# main_v3.net
KiCad netlist of a schematic drawn in EAGLE
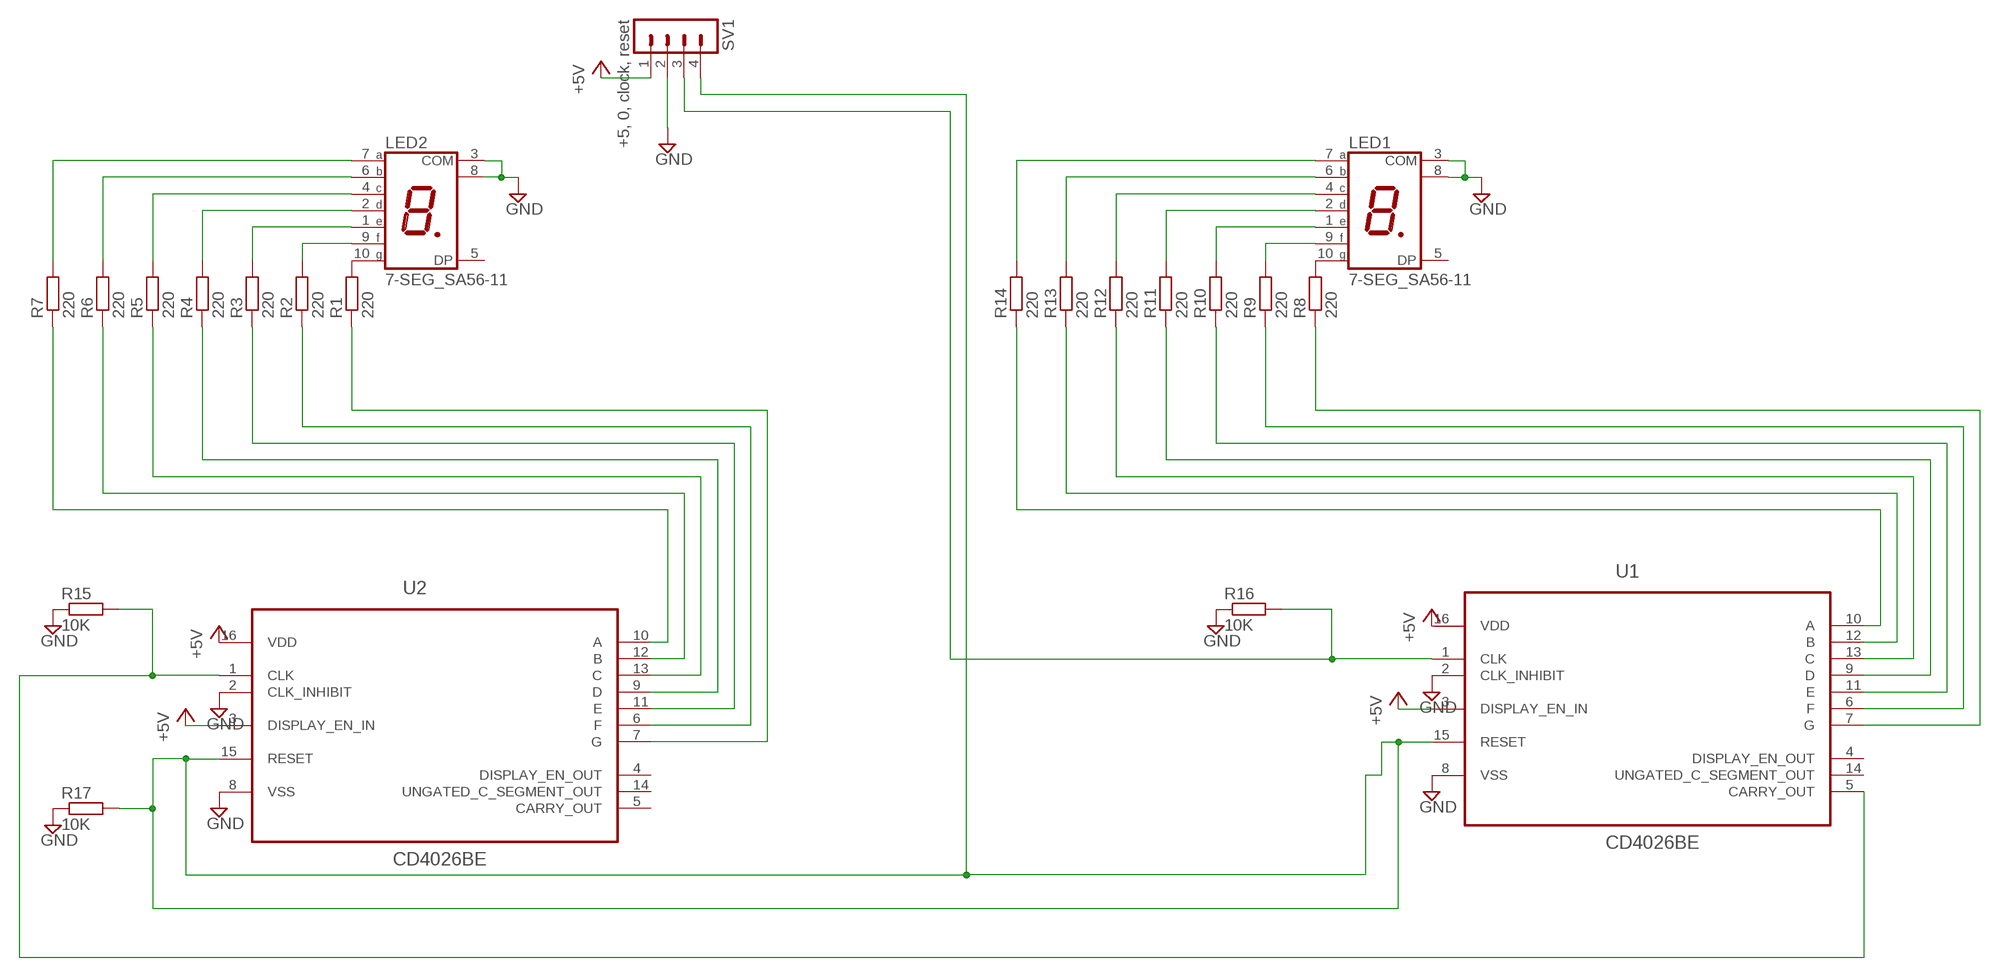
[diagram p0: schematic, sheet 1]

(export (version "E")
  (design (tool "Eeschema 10.0.6"))
  (components
    (comp (ref "LED1")
      (value "7-SEG_SA56-11")
      (footprint "eagle-import:SA56-11")
      (libsource (lib "eagle-import") (part "7-SEG_SA56-11"))
    )
    (comp (ref "LED2")
      (value "7-SEG_SA56-11")
      (footprint "eagle-import:SA56-11")
      (libsource (lib "eagle-import") (part "7-SEG_SA56-11"))
    )
    (comp (ref "R1")
      (value "220")
      (footprint "eagle-import:R0805")
      (libsource (lib "eagle-import") (part "R-EU_R0805"))
    )
    (comp (ref "R2")
      (value "220")
      (footprint "eagle-import:R0805")
      (libsource (lib "eagle-import") (part "R-EU_R0805"))
    )
    (comp (ref "R3")
      (value "220")
      (footprint "eagle-import:R0805")
      (libsource (lib "eagle-import") (part "R-EU_R0805"))
    )
    (comp (ref "R4")
      (value "220")
      (footprint "eagle-import:R0805")
      (libsource (lib "eagle-import") (part "R-EU_R0805"))
    )
    (comp (ref "R5")
      (value "220")
      (footprint "eagle-import:R0805")
      (libsource (lib "eagle-import") (part "R-EU_R0805"))
    )
    (comp (ref "R6")
      (value "220")
      (footprint "eagle-import:R0805")
      (libsource (lib "eagle-import") (part "R-EU_R0805"))
    )
    (comp (ref "R7")
      (value "220")
      (footprint "eagle-import:R0805")
      (libsource (lib "eagle-import") (part "R-EU_R0805"))
    )
    (comp (ref "R8")
      (value "220")
      (footprint "eagle-import:R0805")
      (libsource (lib "eagle-import") (part "R-EU_R0805"))
    )
    (comp (ref "R9")
      (value "220")
      (footprint "eagle-import:R0805")
      (libsource (lib "eagle-import") (part "R-EU_R0805"))
    )
    (comp (ref "R10")
      (value "220")
      (footprint "eagle-import:R0805")
      (libsource (lib "eagle-import") (part "R-EU_R0805"))
    )
    (comp (ref "R11")
      (value "220")
      (footprint "eagle-import:R0805")
      (libsource (lib "eagle-import") (part "R-EU_R0805"))
    )
    (comp (ref "R12")
      (value "220")
      (footprint "eagle-import:R0805")
      (libsource (lib "eagle-import") (part "R-EU_R0805"))
    )
    (comp (ref "R13")
      (value "220")
      (footprint "eagle-import:R0805")
      (libsource (lib "eagle-import") (part "R-EU_R0805"))
    )
    (comp (ref "R14")
      (value "220")
      (footprint "eagle-import:R0805")
      (libsource (lib "eagle-import") (part "R-EU_R0805"))
    )
    (comp (ref "R15")
      (value "10K")
      (footprint "eagle-import:R0805")
      (libsource (lib "eagle-import") (part "R-EU_R0805"))
    )
    (comp (ref "R16")
      (value "10K")
      (footprint "eagle-import:R0805")
      (libsource (lib "eagle-import") (part "R-EU_R0805"))
    )
    (comp (ref "R17")
      (value "10K")
      (footprint "eagle-import:R0805")
      (libsource (lib "eagle-import") (part "R-EU_R0805"))
    )
    (comp (ref "SV1")
      (value "+5, 0, clock, reset")
      (footprint "eagle-import:MA04-1")
      (libsource (lib "eagle-import") (part "MA04-1"))
    )
    (comp (ref "U1")
      (value "CD4026BE")
      (footprint "eagle-import:DIP254P762X508-16")
      (libsource (lib "eagle-import") (part "CD4026BE"))
    )
    (comp (ref "U2")
      (value "CD4026BE")
      (footprint "eagle-import:DIP254P762X508-16")
      (libsource (lib "eagle-import") (part "CD4026BE"))
    )
  )
  (nets
    (net (code "1") (name "+5V") (class "Default")
      (node (ref "SV1") (pin "1") (pinfunction "1_1") (pintype "passive"))
      (node (ref "U1") (pin "16") (pinfunction "VDD_16") (pintype "power_in"))
      (node (ref "U1") (pin "3") (pinfunction "DISPLAY_EN_IN_3") (pintype "input"))
      (node (ref "U2") (pin "16") (pinfunction "VDD_16") (pintype "power_in"))
      (node (ref "U2") (pin "3") (pinfunction "DISPLAY_EN_IN_3") (pintype "input"))
    )
    (net (code "2") (name "GND") (class "Default")
      (node (ref "LED1") (pin "3") (pinfunction "COM_3") (pintype "passive"))
      (node (ref "LED1") (pin "8") (pinfunction "COM_8") (pintype "passive"))
      (node (ref "LED2") (pin "3") (pinfunction "COM_3") (pintype "passive"))
      (node (ref "LED2") (pin "8") (pinfunction "COM_8") (pintype "passive"))
      (node (ref "R15") (pin "1") (pinfunction "1_1") (pintype "passive"))
      (node (ref "R16") (pin "1") (pinfunction "1_1") (pintype "passive"))
      (node (ref "R17") (pin "1") (pinfunction "1_1") (pintype "passive"))
      (node (ref "SV1") (pin "2") (pinfunction "2_2") (pintype "passive"))
      (node (ref "U1") (pin "2") (pinfunction "CLK_INHIBIT_2") (pintype "input"))
      (node (ref "U1") (pin "8") (pinfunction "VSS_8") (pintype "power_in"))
      (node (ref "U2") (pin "2") (pinfunction "CLK_INHIBIT_2") (pintype "input"))
      (node (ref "U2") (pin "8") (pinfunction "VSS_8") (pintype "power_in"))
    )
    (net (code "3") (name "Net-(LED1-A)") (class "Default")
      (node (ref "LED1") (pin "7") (pinfunction "A_7") (pintype "passive"))
      (node (ref "R14") (pin "2") (pinfunction "2_2") (pintype "passive"))
    )
    (net (code "4") (name "Net-(LED1-B)") (class "Default")
      (node (ref "LED1") (pin "6") (pinfunction "B_6") (pintype "passive"))
      (node (ref "R13") (pin "2") (pinfunction "2_2") (pintype "passive"))
    )
    (net (code "5") (name "Net-(LED1-C)") (class "Default")
      (node (ref "LED1") (pin "4") (pinfunction "C_4") (pintype "passive"))
      (node (ref "R12") (pin "2") (pinfunction "2_2") (pintype "passive"))
    )
    (net (code "6") (name "Net-(LED1-D)") (class "Default")
      (node (ref "LED1") (pin "2") (pinfunction "D_2") (pintype "passive"))
      (node (ref "R11") (pin "2") (pinfunction "2_2") (pintype "passive"))
    )
    (net (code "7") (name "Net-(LED1-E)") (class "Default")
      (node (ref "LED1") (pin "1") (pinfunction "E_1") (pintype "passive"))
      (node (ref "R10") (pin "2") (pinfunction "2_2") (pintype "passive"))
    )
    (net (code "8") (name "Net-(LED1-F)") (class "Default")
      (node (ref "LED1") (pin "9") (pinfunction "F_9") (pintype "passive"))
      (node (ref "R9") (pin "2") (pinfunction "2_2") (pintype "passive"))
    )
    (net (code "9") (name "Net-(LED1-G)") (class "Default")
      (node (ref "LED1") (pin "10") (pinfunction "G_10") (pintype "passive"))
      (node (ref "R8") (pin "2") (pinfunction "2_2") (pintype "passive"))
    )
    (net (code "10") (name "Net-(LED2-A)") (class "Default")
      (node (ref "LED2") (pin "7") (pinfunction "A_7") (pintype "passive"))
      (node (ref "R7") (pin "2") (pinfunction "2_2") (pintype "passive"))
    )
    (net (code "11") (name "Net-(LED2-B)") (class "Default")
      (node (ref "LED2") (pin "6") (pinfunction "B_6") (pintype "passive"))
      (node (ref "R6") (pin "2") (pinfunction "2_2") (pintype "passive"))
    )
    (net (code "12") (name "Net-(LED2-C)") (class "Default")
      (node (ref "LED2") (pin "4") (pinfunction "C_4") (pintype "passive"))
      (node (ref "R5") (pin "2") (pinfunction "2_2") (pintype "passive"))
    )
    (net (code "13") (name "Net-(LED2-D)") (class "Default")
      (node (ref "LED2") (pin "2") (pinfunction "D_2") (pintype "passive"))
      (node (ref "R4") (pin "2") (pinfunction "2_2") (pintype "passive"))
    )
    (net (code "14") (name "Net-(LED2-E)") (class "Default")
      (node (ref "LED2") (pin "1") (pinfunction "E_1") (pintype "passive"))
      (node (ref "R3") (pin "2") (pinfunction "2_2") (pintype "passive"))
    )
    (net (code "15") (name "Net-(LED2-F)") (class "Default")
      (node (ref "LED2") (pin "9") (pinfunction "F_9") (pintype "passive"))
      (node (ref "R2") (pin "2") (pinfunction "2_2") (pintype "passive"))
    )
    (net (code "16") (name "Net-(LED2-G)") (class "Default")
      (node (ref "LED2") (pin "10") (pinfunction "G_10") (pintype "passive"))
      (node (ref "R1") (pin "2") (pinfunction "2_2") (pintype "passive"))
    )
    (net (code "17") (name "Net-(U1-A)") (class "Default")
      (node (ref "R14") (pin "1") (pinfunction "1_1") (pintype "passive"))
      (node (ref "U1") (pin "10") (pinfunction "A_10") (pintype "output"))
    )
    (net (code "18") (name "Net-(U1-B)") (class "Default")
      (node (ref "R13") (pin "1") (pinfunction "1_1") (pintype "passive"))
      (node (ref "U1") (pin "12") (pinfunction "B_12") (pintype "output"))
    )
    (net (code "19") (name "Net-(U1-C)") (class "Default")
      (node (ref "R12") (pin "1") (pinfunction "1_1") (pintype "passive"))
      (node (ref "U1") (pin "13") (pinfunction "C_13") (pintype "output"))
    )
    (net (code "20") (name "Net-(U1-CARRY_OUT)") (class "Default")
      (node (ref "R15") (pin "2") (pinfunction "2_2") (pintype "passive"))
      (node (ref "U1") (pin "5") (pinfunction "CARRY_OUT_5") (pintype "output"))
      (node (ref "U2") (pin "1") (pinfunction "CLK_1") (pintype "input"))
    )
    (net (code "21") (name "Net-(U1-CLK)") (class "Default")
      (node (ref "R16") (pin "2") (pinfunction "2_2") (pintype "passive"))
      (node (ref "SV1") (pin "3") (pinfunction "3_3") (pintype "passive"))
      (node (ref "U1") (pin "1") (pinfunction "CLK_1") (pintype "input"))
    )
    (net (code "22") (name "Net-(U1-D)") (class "Default")
      (node (ref "R11") (pin "1") (pinfunction "1_1") (pintype "passive"))
      (node (ref "U1") (pin "9") (pinfunction "D_9") (pintype "output"))
    )
    (net (code "23") (name "Net-(U1-E)") (class "Default")
      (node (ref "R10") (pin "1") (pinfunction "1_1") (pintype "passive"))
      (node (ref "U1") (pin "11") (pinfunction "E_11") (pintype "output"))
    )
    (net (code "24") (name "Net-(U1-F)") (class "Default")
      (node (ref "R9") (pin "1") (pinfunction "1_1") (pintype "passive"))
      (node (ref "U1") (pin "6") (pinfunction "F_6") (pintype "output"))
    )
    (net (code "25") (name "Net-(U1-G)") (class "Default")
      (node (ref "R8") (pin "1") (pinfunction "1_1") (pintype "passive"))
      (node (ref "U1") (pin "7") (pinfunction "G_7") (pintype "output"))
    )
    (net (code "26") (name "Net-(U1-RESET)") (class "Default")
      (node (ref "R17") (pin "2") (pinfunction "2_2") (pintype "passive"))
      (node (ref "SV1") (pin "4") (pinfunction "4_4") (pintype "passive"))
      (node (ref "U1") (pin "15") (pinfunction "RESET_15") (pintype "input"))
      (node (ref "U2") (pin "15") (pinfunction "RESET_15") (pintype "input"))
    )
    (net (code "27") (name "Net-(U2-A)") (class "Default")
      (node (ref "R7") (pin "1") (pinfunction "1_1") (pintype "passive"))
      (node (ref "U2") (pin "10") (pinfunction "A_10") (pintype "output"))
    )
    (net (code "28") (name "Net-(U2-B)") (class "Default")
      (node (ref "R6") (pin "1") (pinfunction "1_1") (pintype "passive"))
      (node (ref "U2") (pin "12") (pinfunction "B_12") (pintype "output"))
    )
    (net (code "29") (name "Net-(U2-C)") (class "Default")
      (node (ref "R5") (pin "1") (pinfunction "1_1") (pintype "passive"))
      (node (ref "U2") (pin "13") (pinfunction "C_13") (pintype "output"))
    )
    (net (code "30") (name "Net-(U2-D)") (class "Default")
      (node (ref "R4") (pin "1") (pinfunction "1_1") (pintype "passive"))
      (node (ref "U2") (pin "9") (pinfunction "D_9") (pintype "output"))
    )
    (net (code "31") (name "Net-(U2-E)") (class "Default")
      (node (ref "R3") (pin "1") (pinfunction "1_1") (pintype "passive"))
      (node (ref "U2") (pin "11") (pinfunction "E_11") (pintype "output"))
    )
    (net (code "32") (name "Net-(U2-F)") (class "Default")
      (node (ref "R2") (pin "1") (pinfunction "1_1") (pintype "passive"))
      (node (ref "U2") (pin "6") (pinfunction "F_6") (pintype "output"))
    )
    (net (code "33") (name "Net-(U2-G)") (class "Default")
      (node (ref "R1") (pin "1") (pinfunction "1_1") (pintype "passive"))
      (node (ref "U2") (pin "7") (pinfunction "G_7") (pintype "output"))
    )
    (net (code "34") (name "unconnected-(LED1-DP-Pad5)") (class "Default")
      (node (ref "LED1") (pin "5") (pinfunction "DP_5") (pintype "passive"))
    )
    (net (code "35") (name "unconnected-(LED2-DP-Pad5)") (class "Default")
      (node (ref "LED2") (pin "5") (pinfunction "DP_5") (pintype "passive"))
    )
    (net (code "36") (name "unconnected-(U1-DISPLAY_EN_OUT-Pad4)") (class "Default")
      (node (ref "U1") (pin "4") (pinfunction "DISPLAY_EN_OUT_4") (pintype "output"))
    )
    (net (code "37") (name "unconnected-(U1-UNGATED_C_SEGMENT_OUT-Pad14)") (class "Default")
      (node (ref "U1") (pin "14") (pinfunction "UNGATED_C_SEGMENT_OUT_14") (pintype "output"))
    )
    (net (code "38") (name "unconnected-(U2-CARRY_OUT-Pad5)") (class "Default")
      (node (ref "U2") (pin "5") (pinfunction "CARRY_OUT_5") (pintype "output"))
    )
    (net (code "39") (name "unconnected-(U2-DISPLAY_EN_OUT-Pad4)") (class "Default")
      (node (ref "U2") (pin "4") (pinfunction "DISPLAY_EN_OUT_4") (pintype "output"))
    )
    (net (code "40") (name "unconnected-(U2-UNGATED_C_SEGMENT_OUT-Pad14)") (class "Default")
      (node (ref "U2") (pin "14") (pinfunction "UNGATED_C_SEGMENT_OUT_14") (pintype "output"))
    )
  )
)
